# brick_i2c_3axis.net
KiCad netlist of a schematic drawn in EAGLE
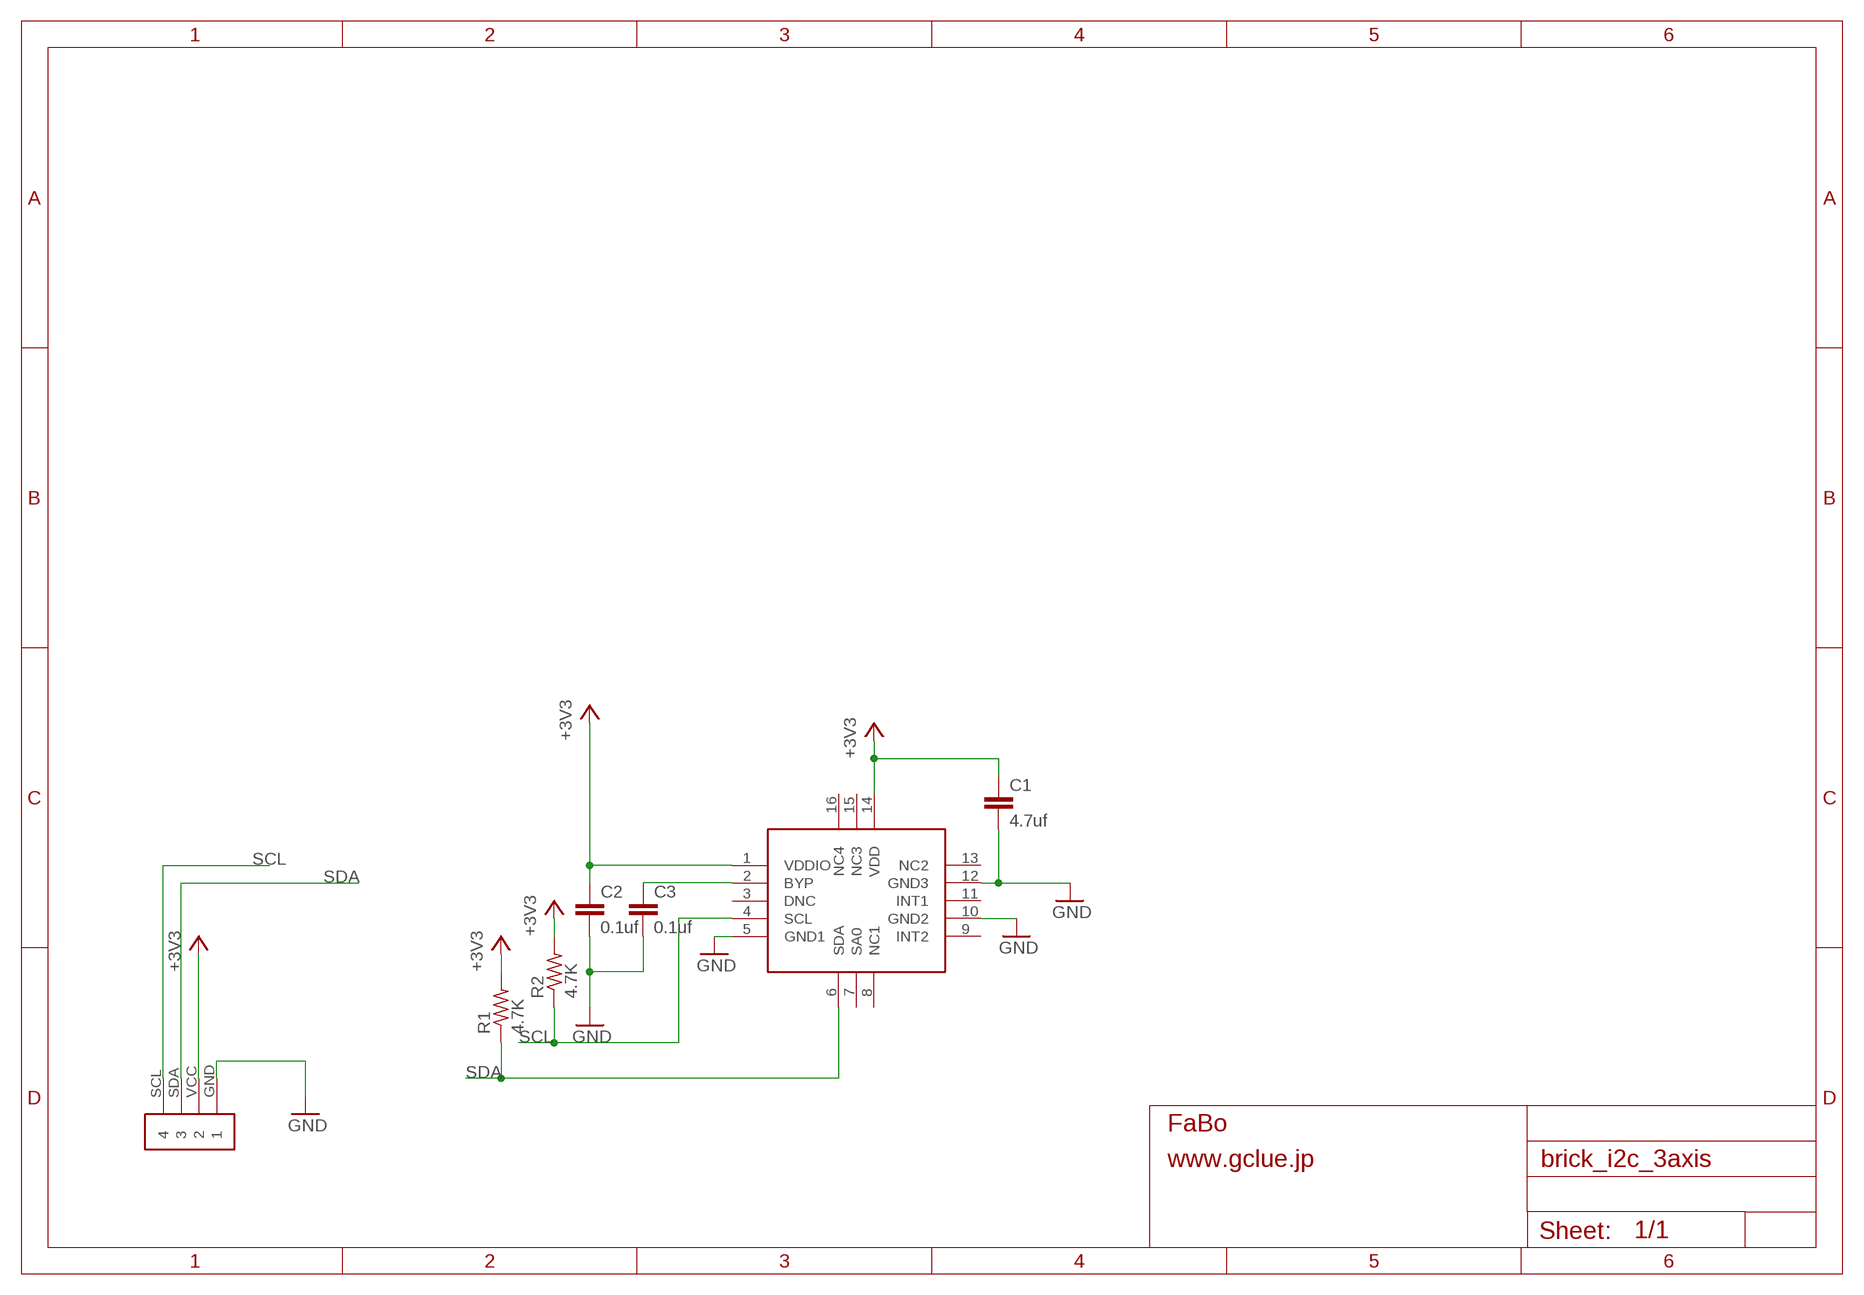
[diagram p0: schematic, sheet 1]

(export (version "E")
  (design (tool "Eeschema 10.0.6"))
  (components
    (comp (ref "C1")
      (value "4.7uf")
      (footprint "eagle-import:C0603")
      (libsource (lib "eagle-import") (part "C-EUC0603"))
    )
    (comp (ref "C2")
      (value "0.1uf")
      (footprint "eagle-import:C0603")
      (libsource (lib "eagle-import") (part "C-EUC0603"))
    )
    (comp (ref "C3")
      (value "0.1uf")
      (footprint "eagle-import:C0603")
      (libsource (lib "eagle-import") (part "C-EUC0603"))
    )
    (comp (ref "MMA1")
      (value "FREESCALE-MMA8451Q")
      (footprint "eagle-import:FREESCALE-MMA8451Q")
      (libsource (lib "eagle-import") (part "FREESCALE-MMA8451Q"))
    )
    (comp (ref "R1")
      (value "4.7K")
      (footprint "eagle-import:R0603")
      (libsource (lib "eagle-import") (part "R-US_R0603"))
    )
    (comp (ref "R2")
      (value "4.7K")
      (footprint "eagle-import:R0603")
      (libsource (lib "eagle-import") (part "R-US_R0603"))
    )
    (comp (ref "U$1")
      (value "BRICK_I2C")
      (footprint "eagle-import:BRICK_I2C")
      (libsource (lib "eagle-import") (part "BRICK_I2C"))
    )
  )
  (nets
    (net (code "1") (name "+3V3") (class "Default")
      (node (ref "C1") (pin "1") (pinfunction "1_1") (pintype "passive"))
      (node (ref "C2") (pin "1") (pinfunction "1_1") (pintype "passive"))
      (node (ref "MMA1") (pin "1") (pinfunction "VDDIO_1") (pintype "bidirectional"))
      (node (ref "MMA1") (pin "14") (pinfunction "VDD_14") (pintype "bidirectional"))
      (node (ref "R1") (pin "2") (pinfunction "2_2") (pintype "passive"))
      (node (ref "R2") (pin "2") (pinfunction "2_2") (pintype "passive"))
      (node (ref "U$1") (pin "VCC") (pinfunction "2_VCC") (pintype "bidirectional"))
    )
    (net (code "2") (name "/SCL") (class "Default")
      (node (ref "MMA1") (pin "4") (pinfunction "SCL_4") (pintype "bidirectional"))
      (node (ref "R2") (pin "1") (pinfunction "1_1") (pintype "passive"))
      (node (ref "U$1") (pin "SCL") (pinfunction "4_SCL") (pintype "bidirectional"))
    )
    (net (code "3") (name "/SDA") (class "Default")
      (node (ref "MMA1") (pin "6") (pinfunction "SDA_6") (pintype "bidirectional"))
      (node (ref "R1") (pin "1") (pinfunction "1_1") (pintype "passive"))
      (node (ref "U$1") (pin "SDA") (pinfunction "3_SDA") (pintype "bidirectional"))
    )
    (net (code "4") (name "GND") (class "Default")
      (node (ref "C1") (pin "2") (pinfunction "2_2") (pintype "passive"))
      (node (ref "C2") (pin "2") (pinfunction "2_2") (pintype "passive"))
      (node (ref "C3") (pin "2") (pinfunction "2_2") (pintype "passive"))
      (node (ref "MMA1") (pin "10") (pinfunction "GND2_10") (pintype "bidirectional"))
      (node (ref "MMA1") (pin "12") (pinfunction "GND3_12") (pintype "bidirectional"))
      (node (ref "MMA1") (pin "5") (pinfunction "GND1_5") (pintype "bidirectional"))
      (node (ref "U$1") (pin "GND") (pinfunction "1_GND") (pintype "bidirectional"))
    )
    (net (code "5") (name "Net-(MMA1-BYP)") (class "Default")
      (node (ref "C3") (pin "1") (pinfunction "1_1") (pintype "passive"))
      (node (ref "MMA1") (pin "2") (pinfunction "BYP_2") (pintype "bidirectional"))
    )
    (net (code "6") (name "unconnected-(MMA1-DNC-Pad3)") (class "Default")
      (node (ref "MMA1") (pin "3") (pinfunction "DNC_3") (pintype "bidirectional"))
    )
    (net (code "7") (name "unconnected-(MMA1-INT1-Pad11)") (class "Default")
      (node (ref "MMA1") (pin "11") (pinfunction "INT1_11") (pintype "bidirectional"))
    )
    (net (code "8") (name "unconnected-(MMA1-INT2-Pad9)") (class "Default")
      (node (ref "MMA1") (pin "9") (pinfunction "INT2_9") (pintype "bidirectional"))
    )
    (net (code "9") (name "unconnected-(MMA1-NC1-Pad8)") (class "Default")
      (node (ref "MMA1") (pin "8") (pinfunction "NC1_8") (pintype "bidirectional"))
    )
    (net (code "10") (name "unconnected-(MMA1-NC2-Pad13)") (class "Default")
      (node (ref "MMA1") (pin "13") (pinfunction "NC2_13") (pintype "bidirectional"))
    )
    (net (code "11") (name "unconnected-(MMA1-NC3-Pad15)") (class "Default")
      (node (ref "MMA1") (pin "15") (pinfunction "NC3_15") (pintype "bidirectional"))
    )
    (net (code "12") (name "unconnected-(MMA1-NC4-Pad16)") (class "Default")
      (node (ref "MMA1") (pin "16") (pinfunction "NC4_16") (pintype "bidirectional"))
    )
    (net (code "13") (name "unconnected-(MMA1-SA0-Pad7)") (class "Default")
      (node (ref "MMA1") (pin "7") (pinfunction "SA0_7") (pintype "bidirectional"))
    )
  )
)
